# 011_BPD_Arduino_Shield.net
KiCad netlist of a schematic drawn in Altium Designer
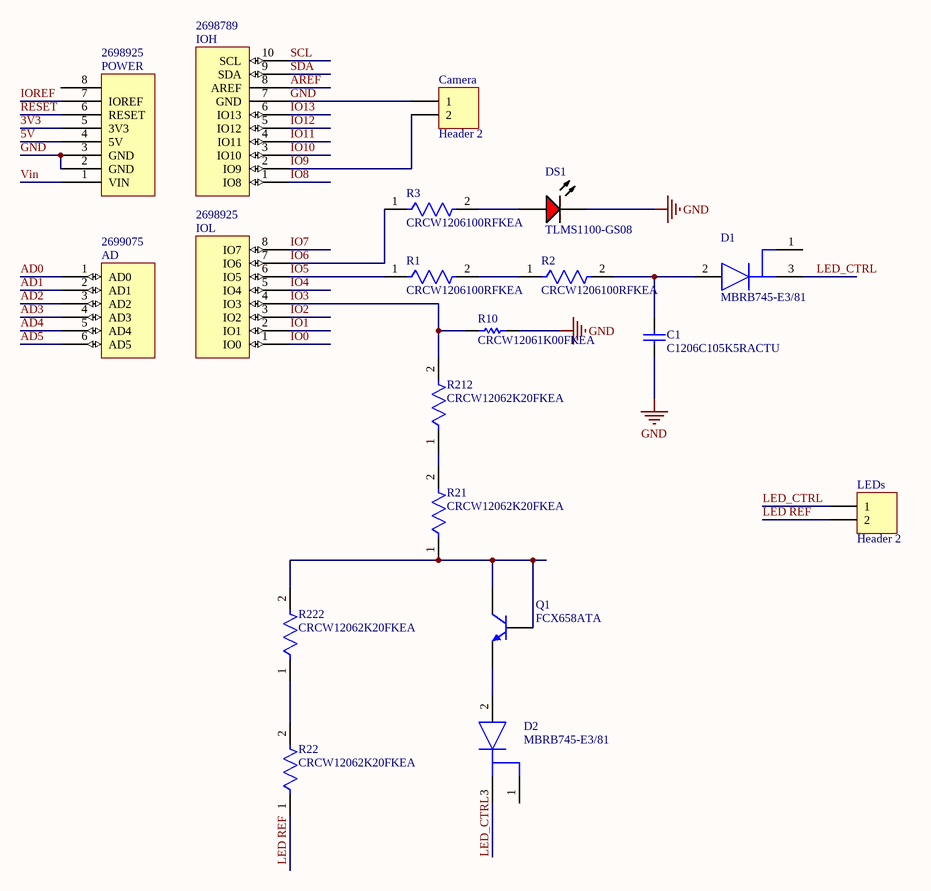
[diagram p0: 011_BPD_Arduino_Shield.SchDoc]

(export (version "E")
  (design (tool "Eeschema 10.0.6"))
  (components
    (comp (ref "AD")
      (value "AD")
      (footprint "Header:Header 6x1 8.5mm")
      (fields (field (name "SUPPLIER PART NUMBER 4") "2699075"))
      (libsource (lib "Header") (part "AD"))
    )
    (comp (ref "C1")
      (value "C1206C105K5RACTU")
      (footprint "CAPC3216X110X50LL20T25")
      (description "Chip Capacitor, 1 uF, +/- 10%, 50 V, -55 to 125 degC, 1206 (3216 Metric), RoHS, Tape and Reel")
      (fields (field (name "MANUFACTURER") "Kemet") (field (name "TOLERANCE") "10%"))
      (libsource (lib "Altium Content Vault") (part "CAP-NP-2"))
    )
    (comp (ref "Camera")
      (value "Header 2")
      (footprint "HDR1X2")
      (description "Header, 2-Pin")
      (fields (field (name "PUBLISHER") "Altium Limited"))
      (libsource (lib "Miscellaneous Connectors") (part "Header 2"))
    )
    (comp (ref "D1")
      (value "MBRB745-E3/81")
      (footprint "FP-MBRB745-E3-81-MFG")
      (description "DIODE SCHOTTKY 45V 7.5A TO263AB")
      (fields
        (field (name "OCTOPART") "https://octopart.com/mbrb745-e3%2F81-vishay-42182719")
        (field (name "MANUFACTURER") "Vishay")
      )
      (libsource (lib "Altium Content Vault") (part "a1da37f982aa56c48f018892279e757"))
    )
    (comp (ref "D2")
      (value "MBRB745-E3/81")
      (footprint "FP-MBRB745-E3-81-MFG")
      (description "DIODE SCHOTTKY 45V 7.5A TO263AB")
      (fields
        (field (name "OCTOPART") "https://octopart.com/mbrb745-e3%2F81-vishay-42182719")
        (field (name "MANUFACTURER") "Vishay")
      )
      (libsource (lib "Altium Content Vault") (part "a1da37f982aa56c48f018892279e757"))
    )
    (comp (ref "DS1")
      (value "TLMS1100-GS08")
      (footprint "VISH-TLMX1100_V")
      (description "LED, RED, 2.1 V, -40 to 100 degC, 2-Pin SMD (0603), RoHS, Tape and Reel")
      (fields (field (name "TOLERANCE") "5%"))
      (libsource (lib "Altium Content Vault") (part "LED-RED-AK-2"))
    )
    (comp (ref "IOH")
      (value "IOH")
      (footprint "Header:Header 10x1 8.5mm")
      (fields (field (name "SUPPLIER PART NUMBER 3") "2698789"))
      (libsource (lib "Header") (part "IOH"))
    )
    (comp (ref "IOL")
      (value "IOL")
      (footprint "Header 8x1 8.5mm")
      (fields (field (name "SUPPLIER PART NUMBER 4") "2698925"))
      (libsource (lib "Header") (part "IOL"))
    )
    (comp (ref "LEDs")
      (value "Header 2")
      (footprint "HDR1X2")
      (description "Header, 2-Pin")
      (fields (field (name "PUBLISHER") "Altium Limited"))
      (libsource (lib "Miscellaneous Connectors") (part "Header 2"))
    )
    (comp (ref "POWER")
      (value "POWER_UNO")
      (footprint "Header 8x1 8.5mm")
      (fields (field (name "SUPPLIER PART NUMBER 4") "2698925"))
      (libsource (lib "Header") (part "POWER_UNO"))
    )
    (comp (ref "Q1")
      (value "FCX658ATA")
      (footprint "DIOD-SOT89-3_V")
      (fields (field (name "MANUFACTURER") "Diodes Inc"))
      (libsource (lib "Altium Content Vault") (part "DIOD-NPN_B1C2E3-3"))
    )
    (comp (ref "R1")
      (value "CRCW1206100RFKEA")
      (footprint "FP-CRCW1206-e3-MFG")
      (description "RES Thick Film, 100Ω, 1%, 0.25W, 100ppm/°C, 1206")
      (fields (field (name "TOLERANCE") "1%"))
      (libsource (lib "Altium Content Vault") (part "1029c3af85768c4190bb7ad29bc67b5"))
    )
    (comp (ref "R2")
      (value "CRCW1206100RFKEA")
      (footprint "FP-CRCW1206-e3-MFG")
      (description "RES Thick Film, 100Ω, 1%, 0.25W, 100ppm/°C, 1206")
      (fields (field (name "TOLERANCE") "1%"))
      (libsource (lib "Altium Content Vault") (part "1029c3af85768c4190bb7ad29bc67b5"))
    )
    (comp (ref "R3")
      (value "CRCW1206100RFKEA")
      (footprint "FP-CRCW1206-e3-MFG")
      (description "RES Thick Film, 100Ω, 1%, 0.25W, 100ppm/°C, 1206")
      (fields (field (name "TOLERANCE") "1%"))
      (libsource (lib "Altium Content Vault") (part "1029c3af85768c4190bb7ad29bc67b5"))
    )
    (comp (ref "R10")
      (value "CRCW12061K00FKEA")
      (footprint "RESC3216X60X45ML15T20")
      (description "Chip Resistor, 1 KOhm, +/- 1%, 0.25 W, -55 to 155 degC, 1206 (3216 Metric), RoHS, Tape and Reel")
      (fields (field (name "MANUFACTURER") "Vishay Semiconductor") (field (name "TOLERANCE") "1%"))
      (libsource (lib "Altium Content Vault") (part "RES-2"))
    )
    (comp (ref "R21")
      (value "CRCW12062K20FKEA")
      (footprint "FP-CRCW1206-e3-IPC_C")
      (description "RES Thick Film, 1kΩ, 1%, 0.25W, 100ppm/°C, 1206")
      (fields (field (name "TOLERANCE") "1%"))
      (libsource (lib "Altium Content Vault") (part "1029c3af85768c4190bb7ad29bc67b5"))
    )
    (comp (ref "R22")
      (value "CRCW12062K20FKEA")
      (footprint "FP-CRCW1206-e3-IPC_C")
      (description "RES Thick Film, 1kΩ, 1%, 0.25W, 100ppm/°C, 1206")
      (fields (field (name "TOLERANCE") "1%"))
      (libsource (lib "Altium Content Vault") (part "1029c3af85768c4190bb7ad29bc67b5"))
    )
    (comp (ref "R212")
      (value "CRCW12062K20FKEA")
      (footprint "FP-CRCW1206-e3-IPC_C")
      (description "RES Thick Film, 1kΩ, 1%, 0.25W, 100ppm/°C, 1206")
      (fields (field (name "TOLERANCE") "1%"))
      (libsource (lib "Altium Content Vault") (part "1029c3af85768c4190bb7ad29bc67b5"))
    )
    (comp (ref "R222")
      (value "CRCW12062K20FKEA")
      (footprint "FP-CRCW1206-e3-IPC_C")
      (description "RES Thick Film, 1kΩ, 1%, 0.25W, 100ppm/°C, 1206")
      (fields (field (name "TOLERANCE") "1%"))
      (libsource (lib "Altium Content Vault") (part "1029c3af85768c4190bb7ad29bc67b5"))
    )
  )
  (nets
    (net (code "1") (name "/3V3") (class "Default")
      (node (ref "POWER") (pin "5") (pinfunction "3V3_5") (pintype "power_in"))
    )
    (net (code "2") (name "/5V") (class "Default")
      (node (ref "POWER") (pin "4") (pinfunction "5V_4") (pintype "power_in"))
    )
    (net (code "4") (name "/AD0") (class "Default")
      (node (ref "AD") (pin "1") (pinfunction "AD0_1") (pintype "bidirectional"))
    )
    (net (code "5") (name "/AD1") (class "Default")
      (node (ref "AD") (pin "2") (pinfunction "AD1_2") (pintype "bidirectional"))
    )
    (net (code "6") (name "/AD2") (class "Default")
      (node (ref "AD") (pin "3") (pinfunction "AD2_3") (pintype "bidirectional"))
    )
    (net (code "7") (name "/AD3") (class "Default")
      (node (ref "AD") (pin "4") (pinfunction "AD3_4") (pintype "bidirectional"))
    )
    (net (code "8") (name "/AD4") (class "Default")
      (node (ref "AD") (pin "5") (pinfunction "AD4_5") (pintype "bidirectional"))
    )
    (net (code "9") (name "/AD5") (class "Default")
      (node (ref "AD") (pin "6") (pinfunction "AD5_6") (pintype "bidirectional"))
    )
    (net (code "10") (name "/AREF") (class "Default")
      (node (ref "IOH") (pin "8") (pinfunction "AREF_8") (pintype "passive"))
    )
    (net (code "11") (name "/IO0") (class "Default")
      (node (ref "IOL") (pin "1") (pinfunction "IO0_1") (pintype "bidirectional"))
    )
    (net (code "12") (name "/IO1") (class "Default")
      (node (ref "IOL") (pin "2") (pinfunction "IO1_2") (pintype "bidirectional"))
    )
    (net (code "13") (name "/IO2") (class "Default")
      (node (ref "IOL") (pin "3") (pinfunction "IO2_3") (pintype "bidirectional"))
    )
    (net (code "14") (name "/IO3") (class "Default")
      (node (ref "IOL") (pin "4") (pinfunction "IO3_4") (pintype "bidirectional"))
      (node (ref "R10") (pin "1") (pinfunction "1_1") (pintype "passive"))
      (node (ref "R212") (pin "2") (pinfunction "2_2") (pintype "passive"))
    )
    (net (code "15") (name "/IO4") (class "Default")
      (node (ref "IOL") (pin "5") (pinfunction "IO4_5") (pintype "bidirectional"))
    )
    (net (code "16") (name "/IO5") (class "Default")
      (node (ref "IOL") (pin "6") (pinfunction "IO5_6") (pintype "bidirectional"))
      (node (ref "R1") (pin "1") (pinfunction "1_1") (pintype "passive"))
    )
    (net (code "17") (name "/IO6") (class "Default")
      (node (ref "IOL") (pin "7") (pinfunction "IO6_7") (pintype "bidirectional"))
      (node (ref "R3") (pin "1") (pinfunction "1_1") (pintype "passive"))
    )
    (net (code "18") (name "/IO7") (class "Default")
      (node (ref "IOL") (pin "8") (pinfunction "IO7_8") (pintype "bidirectional"))
    )
    (net (code "19") (name "/IO8") (class "Default")
      (node (ref "IOH") (pin "1") (pinfunction "IO8_1") (pintype "bidirectional"))
    )
    (net (code "20") (name "/IO9") (class "Default")
      (node (ref "Camera") (pin "2") (pinfunction "2_2") (pintype "passive"))
      (node (ref "IOH") (pin "2") (pinfunction "IO9_2") (pintype "bidirectional"))
    )
    (net (code "21") (name "/IO10") (class "Default")
      (node (ref "IOH") (pin "3") (pinfunction "IO10_3") (pintype "bidirectional"))
    )
    (net (code "22") (name "/IO11") (class "Default")
      (node (ref "IOH") (pin "4") (pinfunction "IO11_4") (pintype "bidirectional"))
    )
    (net (code "23") (name "/IO12") (class "Default")
      (node (ref "IOH") (pin "5") (pinfunction "IO12_5") (pintype "bidirectional"))
    )
    (net (code "24") (name "/IO13") (class "Default")
      (node (ref "IOH") (pin "6") (pinfunction "IO13_6") (pintype "bidirectional"))
    )
    (net (code "25") (name "/IOREF") (class "Default")
      (node (ref "POWER") (pin "7") (pinfunction "IOREF_7") (pintype "power_in"))
    )
    (net (code "26") (name "/LED REF") (class "Default")
      (node (ref "LEDs") (pin "2") (pinfunction "2_2") (pintype "passive"))
      (node (ref "R22") (pin "1") (pinfunction "1_1") (pintype "passive"))
    )
    (net (code "27") (name "/LED_CTRL") (class "Default")
      (node (ref "D1") (pin "3") (pinfunction "C_3") (pintype "passive"))
      (node (ref "D2") (pin "3") (pinfunction "C_3") (pintype "passive"))
      (node (ref "LEDs") (pin "1") (pinfunction "1_1") (pintype "passive"))
    )
    (net (code "28") (name "/RESET") (class "Default")
      (node (ref "POWER") (pin "6") (pinfunction "RESET_6") (pintype "passive"))
    )
    (net (code "29") (name "/SCL") (class "Default")
      (node (ref "IOH") (pin "10") (pinfunction "SCL_10") (pintype "bidirectional"))
    )
    (net (code "30") (name "/SDA") (class "Default")
      (node (ref "IOH") (pin "9") (pinfunction "SDA_9") (pintype "bidirectional"))
    )
    (net (code "31") (name "/Vin") (class "Default")
      (node (ref "POWER") (pin "1") (pinfunction "VIN_1") (pintype "power_in"))
    )
    (net (code "32") (name "GND") (class "Default")
      (node (ref "C1") (pin "1") (pinfunction "1_1") (pintype "passive"))
      (node (ref "Camera") (pin "1") (pinfunction "1_1") (pintype "passive"))
      (node (ref "DS1") (pin "2") (pinfunction "K_2") (pintype "passive"))
      (node (ref "IOH") (pin "7") (pinfunction "GND_7") (pintype "power_in"))
      (node (ref "POWER") (pin "2") (pinfunction "GND_2") (pintype "power_in"))
      (node (ref "POWER") (pin "3") (pinfunction "GND_3") (pintype "power_in"))
      (node (ref "R10") (pin "2") (pinfunction "2_2") (pintype "passive"))
    )
    (net (code "33") (name "Net-(D1-A)") (class "Default")
      (node (ref "C1") (pin "2") (pinfunction "2_2") (pintype "passive"))
      (node (ref "D1") (pin "2") (pinfunction "A_2") (pintype "passive"))
      (node (ref "R2") (pin "2") (pinfunction "2_2") (pintype "passive"))
    )
    (net (code "34") (name "Net-(D2-A)") (class "Default")
      (node (ref "D2") (pin "2") (pinfunction "A_2") (pintype "passive"))
      (node (ref "Q1") (pin "3") (pinfunction "E_3") (pintype "passive"))
    )
    (net (code "35") (name "Net-(DS1-A)") (class "Default")
      (node (ref "DS1") (pin "1") (pinfunction "A_1") (pintype "passive"))
      (node (ref "R3") (pin "2") (pinfunction "2_2") (pintype "passive"))
    )
    (net (code "36") (name "Net-(Q1-B)") (class "Default")
      (node (ref "Q1") (pin "1") (pinfunction "B_1") (pintype "passive"))
      (node (ref "Q1") (pin "2") (pinfunction "C_2") (pintype "passive"))
      (node (ref "R21") (pin "1") (pinfunction "1_1") (pintype "passive"))
      (node (ref "R222") (pin "2") (pinfunction "2_2") (pintype "passive"))
    )
    (net (code "37") (name "Net-(R1-Pad2)") (class "Default")
      (node (ref "R1") (pin "2") (pinfunction "2_2") (pintype "passive"))
      (node (ref "R2") (pin "1") (pinfunction "1_1") (pintype "passive"))
    )
    (net (code "38") (name "Net-(R21-Pad2)") (class "Default")
      (node (ref "R21") (pin "2") (pinfunction "2_2") (pintype "passive"))
      (node (ref "R212") (pin "1") (pinfunction "1_1") (pintype "passive"))
    )
    (net (code "39") (name "Net-(R22-Pad2)") (class "Default")
      (node (ref "R22") (pin "2") (pinfunction "2_2") (pintype "passive"))
      (node (ref "R222") (pin "1") (pinfunction "1_1") (pintype "passive"))
    )
    (net (code "40") (name "unconnected-(D1-C-Pad1)") (class "Default")
      (node (ref "D1") (pin "1") (pinfunction "C_1") (pintype "passive"))
    )
    (net (code "41") (name "unconnected-(D2-C-Pad1)") (class "Default")
      (node (ref "D2") (pin "1") (pinfunction "C_1") (pintype "passive"))
    )
    (net (code "42") (name "unconnected-(POWER-Pad8)") (class "Default")
      (node (ref "POWER") (pin "8") (pintype "passive"))
    )
  )
)
